# Trail-Traffic-Counter-Board.net
KiCad netlist of a schematic drawn in EAGLE
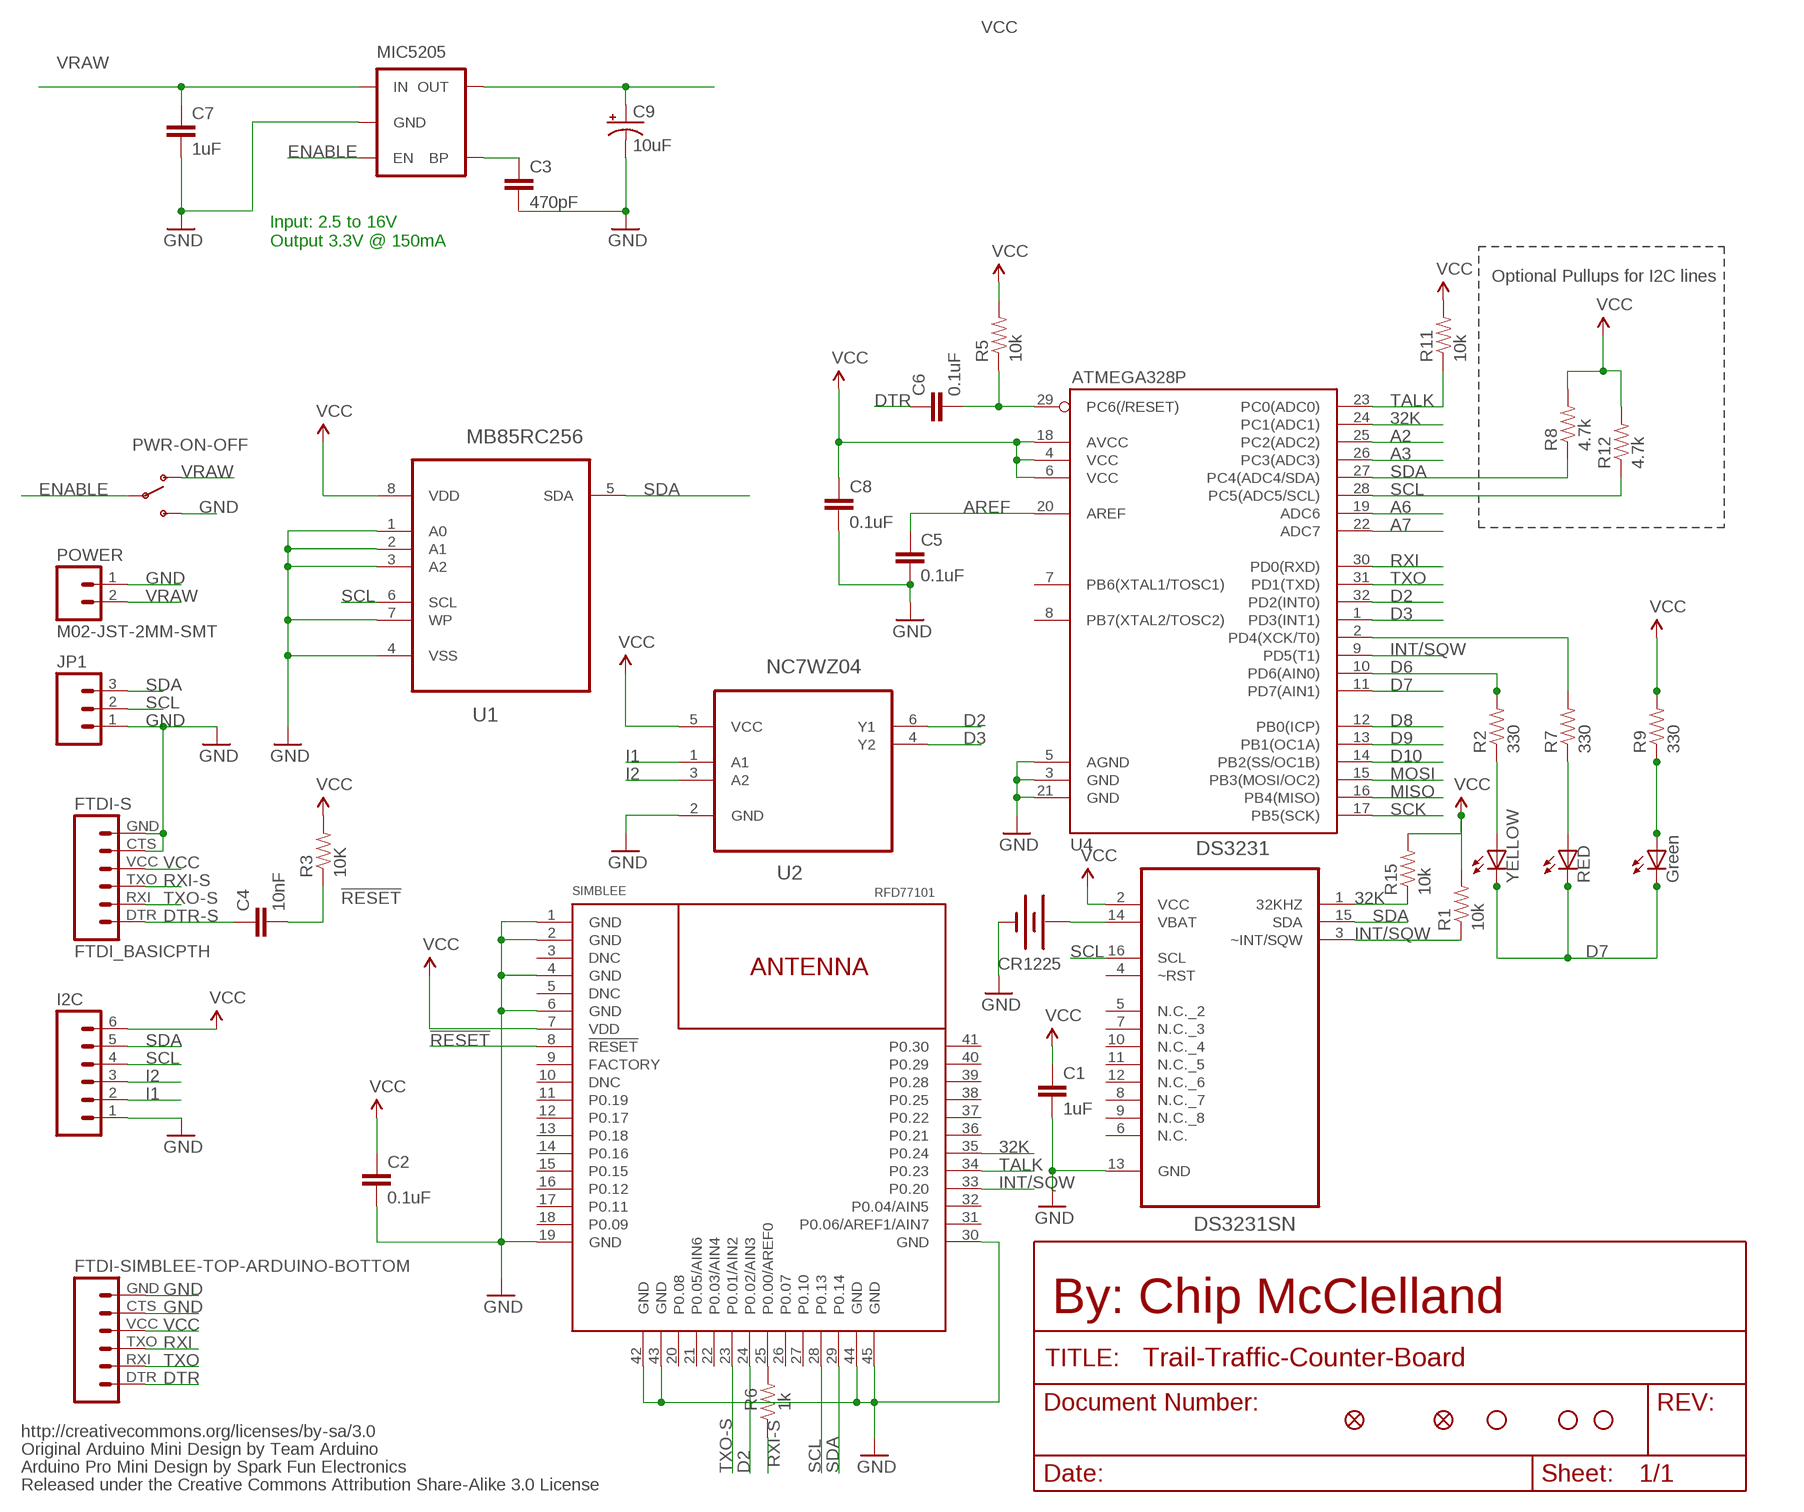
[diagram p0: schematic, sheet 1]

(export (version "E")
  (design (tool "Eeschema 10.0.6"))
  (components
    (comp (ref "ATMEGA328P")
      (value "U4")
      (footprint "eagle-import:TQFP32-08")
      (libsource (lib "eagle-import") (part "ATMEGA168"))
    )
    (comp (ref "C1")
      (value "1uF")
      (footprint "eagle-import:0805")
      (libsource (lib "eagle-import") (part "CAP0805"))
    )
    (comp (ref "C2")
      (value "0.1uF")
      (footprint "eagle-import:0805")
      (libsource (lib "eagle-import") (part "CAP0805"))
    )
    (comp (ref "C3")
      (value "470pF")
      (footprint "eagle-import:0805")
      (libsource (lib "eagle-import") (part "SparkFun-Passives_CAP0805"))
    )
    (comp (ref "C4")
      (value "10nF")
      (footprint "eagle-import:0805")
      (libsource (lib "eagle-import") (part "SparkFun-Passives_CAP0805"))
    )
    (comp (ref "C5")
      (value "0.1uF")
      (footprint "eagle-import:0805")
      (libsource (lib "eagle-import") (part "CAP0805"))
    )
    (comp (ref "C6")
      (value "0.1uF")
      (footprint "eagle-import:0805")
      (libsource (lib "eagle-import") (part "CAP0805"))
    )
    (comp (ref "C7")
      (value "1uF")
      (footprint "eagle-import:0805")
      (libsource (lib "eagle-import") (part "SparkFun-Passives_CAP0805"))
    )
    (comp (ref "C8")
      (value "0.1uF")
      (footprint "eagle-import:0805")
      (libsource (lib "eagle-import") (part "CAP0805"))
    )
    (comp (ref "C9")
      (value "10uF")
      (footprint "eagle-import:EIA3216")
      (libsource (lib "eagle-import") (part "CAP_POL1206"))
    )
    (comp (ref "CR1225")
      (value "BATTERY12MM")
      (footprint "eagle-import:BATTCON_12MM")
      (libsource (lib "eagle-import") (part "BATTERY12MM"))
    )
    (comp (ref "DS3231")
      (value "DS3231SN")
      (footprint "eagle-import:SOIC127P1032X265-16N")
      (fields (field (name "MPN") "DS3231SN#"))
      (libsource (lib "eagle-import") (part "DS3231SN"))
    )
    (comp (ref "FID1")
      (value "FIDUCIALUFIDUCIAL")
      (footprint "eagle-import:MICRO-FIDUCIAL")
      (libsource (lib "eagle-import") (part "FIDUCIALUFIDUCIAL"))
    )
    (comp (ref "FID2")
      (value "FIDUCIALUFIDUCIAL")
      (footprint "eagle-import:MICRO-FIDUCIAL")
      (libsource (lib "eagle-import") (part "FIDUCIALUFIDUCIAL"))
    )
    (comp (ref "FTDI-S")
      (value "FTDI_BASICPTH")
      (footprint "eagle-import:FTDI_BASIC")
      (libsource (lib "eagle-import") (part "FTDI_BASICPTH"))
    )
    (comp (ref "FTDI-SIMBLEE-TOP-ARDUINO-BOTTOM")
      (value "FTDI Basic")
      (footprint "eagle-import:FTDI_BASIC")
      (libsource (lib "eagle-import") (part "FTDI_BASICPTH"))
    )
    (comp (ref "G")
      (value "Green")
      (footprint "eagle-import:CHIPLED_0805")
      (libsource (lib "eagle-import") (part "LEDCHIPLED_0805"))
    )
    (comp (ref "I2C")
      (value "M06LOCK")
      (footprint "eagle-import:1X06_LOCK")
      (libsource (lib "eagle-import") (part "M06LOCK"))
    )
    (comp (ref "JP1")
      (value "M03LOCK")
      (footprint "eagle-import:1X03_LOCK")
      (libsource (lib "eagle-import") (part "M03LOCK"))
    )
    (comp (ref "JP3")
      (value "STAND-OFF")
      (footprint "eagle-import:STAND-OFF")
      (libsource (lib "eagle-import") (part "STAND-OFF"))
    )
    (comp (ref "JP4")
      (value "STAND-OFF")
      (footprint "eagle-import:STAND-OFF")
      (libsource (lib "eagle-import") (part "STAND-OFF"))
    )
    (comp (ref "JP6")
      (value "STAND-OFF")
      (footprint "eagle-import:STAND-OFF")
      (libsource (lib "eagle-import") (part "STAND-OFF"))
    )
    (comp (ref "MB85RC256")
      (value "U1")
      (footprint "eagle-import:SOIC127P600X175-8N")
      (fields (field (name "MPN") "MB85RC128PNF-G-JNE1"))
      (libsource (lib "eagle-import") (part "MB85RC128PNF-G-JNE1"))
    )
    (comp (ref "MIC5205")
      (value "MIC52053.3V")
      (footprint "eagle-import:SOT23-5")
      (libsource (lib "eagle-import") (part "MIC52053.3V"))
    )
    (comp (ref "NC7WZ04")
      (value "U2")
      (footprint "eagle-import:SOT65P210X110-6N")
      (fields (field (name "MPN") "NC7WZ04P6X"))
      (libsource (lib "eagle-import") (part "NC7WZ04P6X"))
    )
    (comp (ref "POWER")
      (value "M02-JST-2MM-SMT")
      (footprint "eagle-import:JST-2-SMD")
      (libsource (lib "eagle-import") (part "M02-JST-2MM-SMT"))
    )
    (comp (ref "PWR-ON-OFF")
      (value "SWITCH-SPDTPTH")
      (footprint "eagle-import:SWITCH-SPDT")
      (libsource (lib "eagle-import") (part "SWITCH-SPDTPTH"))
    )
    (comp (ref "R")
      (value "RED")
      (footprint "eagle-import:CHIPLED_0805")
      (libsource (lib "eagle-import") (part "LEDCHIPLED_0805"))
    )
    (comp (ref "R1")
      (value "10k")
      (footprint "eagle-import:0805")
      (libsource (lib "eagle-import") (part "RESISTOR0805-RES"))
    )
    (comp (ref "R2")
      (value "330")
      (footprint "eagle-import:0603-RES")
      (libsource (lib "eagle-import") (part "RESISTOR0603"))
    )
    (comp (ref "R3")
      (value "10K")
      (footprint "eagle-import:0805")
      (libsource (lib "eagle-import") (part "RESISTOR0805-RES"))
    )
    (comp (ref "R5")
      (value "10k")
      (footprint "eagle-import:0805")
      (libsource (lib "eagle-import") (part "RESISTOR0805-RES"))
    )
    (comp (ref "R6")
      (value "1k")
      (footprint "eagle-import:0805")
      (libsource (lib "eagle-import") (part "RESISTOR0805-RES"))
    )
    (comp (ref "R7")
      (value "330")
      (footprint "eagle-import:0603-RES")
      (libsource (lib "eagle-import") (part "RESISTOR0603"))
    )
    (comp (ref "R8")
      (value "4.7k")
      (footprint "eagle-import:0805")
      (libsource (lib "eagle-import") (part "SparkFun-Resistors_RESISTOR0805-RES"))
    )
    (comp (ref "R9")
      (value "330")
      (footprint "eagle-import:0603-RES")
      (libsource (lib "eagle-import") (part "RESISTOR0603"))
    )
    (comp (ref "R11")
      (value "10k")
      (footprint "eagle-import:0805")
      (libsource (lib "eagle-import") (part "RESISTOR0805-RES"))
    )
    (comp (ref "R12")
      (value "4.7k")
      (footprint "eagle-import:0805")
      (libsource (lib "eagle-import") (part "SparkFun-Resistors_RESISTOR0805-RES"))
    )
    (comp (ref "R15")
      (value "10k")
      (footprint "eagle-import:0805")
      (libsource (lib "eagle-import") (part "RESISTOR0805-RES"))
    )
    (comp (ref "SIMBLEE")
      (value "RFD77101")
      (footprint "eagle-import:RFD77101")
      (libsource (lib "eagle-import") (part "RFD77101"))
    )
    (comp (ref "Y")
      (value "YELLOW")
      (footprint "eagle-import:CHIPLED_0805")
      (libsource (lib "eagle-import") (part "LEDCHIPLED_0805"))
    )
  )
  (nets
    (net (code "1") (name "/32K") (class "Default")
      (node (ref "ATMEGA328P") (pin "24") (pinfunction "PC1(ADC1)_24") (pintype "bidirectional"))
      (node (ref "DS3231") (pin "1") (pinfunction "32KHZ_1") (pintype "output"))
      (node (ref "R15") (pin "1") (pinfunction "1_1") (pintype "passive"))
      (node (ref "SIMBLEE") (pin "35") (pinfunction "P0.24_35") (pintype "bidirectional"))
    )
    (net (code "2") (name "/A2") (class "Default")
      (node (ref "ATMEGA328P") (pin "25") (pinfunction "PC2(ADC2)_25") (pintype "bidirectional"))
    )
    (net (code "3") (name "/A3") (class "Default")
      (node (ref "ATMEGA328P") (pin "26") (pinfunction "PC3(ADC3)_26") (pintype "bidirectional"))
    )
    (net (code "4") (name "/A6") (class "Default")
      (node (ref "ATMEGA328P") (pin "19") (pinfunction "ADC6_19") (pintype "bidirectional"))
    )
    (net (code "5") (name "/A7") (class "Default")
      (node (ref "ATMEGA328P") (pin "22") (pinfunction "ADC7_22") (pintype "bidirectional"))
    )
    (net (code "6") (name "/AREF") (class "Default")
      (node (ref "ATMEGA328P") (pin "20") (pinfunction "AREF_20") (pintype "bidirectional"))
      (node (ref "C5") (pin "1") (pinfunction "1_1") (pintype "passive"))
    )
    (net (code "7") (name "/D2") (class "Default")
      (node (ref "ATMEGA328P") (pin "32") (pinfunction "PD2(INT0)_32") (pintype "bidirectional"))
      (node (ref "NC7WZ04") (pin "6") (pinfunction "Y1_6") (pintype "output"))
      (node (ref "SIMBLEE") (pin "24") (pinfunction "P0.02/AIN3_24") (pintype "bidirectional"))
    )
    (net (code "8") (name "/D3") (class "Default")
      (node (ref "ATMEGA328P") (pin "1") (pinfunction "PD3(INT1)_1") (pintype "bidirectional"))
      (node (ref "NC7WZ04") (pin "4") (pinfunction "Y2_4") (pintype "output"))
    )
    (net (code "9") (name "/D6") (class "Default")
      (node (ref "ATMEGA328P") (pin "10") (pinfunction "PD6(AIN0)_10") (pintype "bidirectional"))
      (node (ref "R2") (pin "2") (pinfunction "2_2") (pintype "passive"))
    )
    (net (code "10") (name "/D7") (class "Default")
      (node (ref "ATMEGA328P") (pin "11") (pinfunction "PD7(AIN1)_11") (pintype "bidirectional"))
      (node (ref "G") (pin "C") (pinfunction "C_C") (pintype "passive"))
      (node (ref "R") (pin "C") (pinfunction "C_C") (pintype "passive"))
      (node (ref "Y") (pin "C") (pinfunction "C_C") (pintype "passive"))
    )
    (net (code "11") (name "/D8") (class "Default")
      (node (ref "ATMEGA328P") (pin "12") (pinfunction "PB0(ICP)_12") (pintype "bidirectional"))
    )
    (net (code "12") (name "/D9") (class "Default")
      (node (ref "ATMEGA328P") (pin "13") (pinfunction "PB1(OC1A)_13") (pintype "bidirectional"))
    )
    (net (code "13") (name "/D10") (class "Default")
      (node (ref "ATMEGA328P") (pin "14") (pinfunction "PB2(SS/OC1B)_14") (pintype "bidirectional"))
    )
    (net (code "14") (name "/DTR") (class "Default")
      (node (ref "C6") (pin "1") (pinfunction "1_1") (pintype "passive"))
      (node (ref "FTDI-SIMBLEE-TOP-ARDUINO-BOTTOM") (pin "DTR") (pinfunction "1_DTR") (pintype "passive"))
    )
    (net (code "15") (name "/DTR-S") (class "Default")
      (node (ref "C4") (pin "1") (pinfunction "1_1") (pintype "passive"))
      (node (ref "FTDI-S") (pin "DTR") (pinfunction "1_DTR") (pintype "passive"))
    )
    (net (code "16") (name "/ENABLE") (class "Default")
      (node (ref "MIC5205") (pin "3") (pinfunction "EN_3") (pintype "input"))
      (node (ref "PWR-ON-OFF") (pin "2") (pinfunction "P_2") (pintype "passive"))
    )
    (net (code "17") (name "/I1") (class "Default")
      (node (ref "I2C") (pin "2") (pinfunction "2_2") (pintype "passive"))
      (node (ref "NC7WZ04") (pin "1") (pinfunction "A1_1") (pintype "input"))
    )
    (net (code "18") (name "/I2") (class "Default")
      (node (ref "I2C") (pin "3") (pinfunction "3_3") (pintype "passive"))
      (node (ref "NC7WZ04") (pin "3") (pinfunction "A2_3") (pintype "input"))
    )
    (net (code "19") (name "/INT{slash}SQW") (class "Default")
      (node (ref "ATMEGA328P") (pin "9") (pinfunction "PD5(T1)_9") (pintype "bidirectional"))
      (node (ref "DS3231") (pin "3") (pinfunction "~{INT/SQW}_3") (pintype "output"))
      (node (ref "R1") (pin "1") (pinfunction "1_1") (pintype "passive"))
      (node (ref "SIMBLEE") (pin "33") (pinfunction "P0.20_33") (pintype "bidirectional"))
    )
    (net (code "20") (name "/MISO") (class "Default")
      (node (ref "ATMEGA328P") (pin "16") (pinfunction "PB4(MISO)_16") (pintype "bidirectional"))
    )
    (net (code "21") (name "/MOSI") (class "Default")
      (node (ref "ATMEGA328P") (pin "15") (pinfunction "PB3(MOSI/OC2)_15") (pintype "bidirectional"))
    )
    (net (code "22") (name "/RXI") (class "Default")
      (node (ref "ATMEGA328P") (pin "30") (pinfunction "PD0(RXD)_30") (pintype "bidirectional"))
      (node (ref "FTDI-SIMBLEE-TOP-ARDUINO-BOTTOM") (pin "TXO") (pinfunction "3_TXO") (pintype "passive"))
    )
    (net (code "23") (name "/RXI-S") (class "Default")
      (node (ref "FTDI-S") (pin "TXO") (pinfunction "3_TXO") (pintype "passive"))
      (node (ref "R6") (pin "1") (pinfunction "1_1") (pintype "passive"))
    )
    (net (code "24") (name "/SCK") (class "Default")
      (node (ref "ATMEGA328P") (pin "17") (pinfunction "PB5(SCK)_17") (pintype "bidirectional"))
    )
    (net (code "25") (name "/SCL") (class "Default")
      (node (ref "ATMEGA328P") (pin "28") (pinfunction "PC5(ADC5/SCL)_28") (pintype "bidirectional"))
      (node (ref "DS3231") (pin "16") (pinfunction "SCL_16") (pintype "input"))
      (node (ref "I2C") (pin "4") (pinfunction "4_4") (pintype "passive"))
      (node (ref "JP1") (pin "2") (pinfunction "2_2") (pintype "passive"))
      (node (ref "MB85RC256") (pin "6") (pinfunction "SCL_6") (pintype "input"))
      (node (ref "R12") (pin "1") (pinfunction "1_1") (pintype "passive"))
      (node (ref "SIMBLEE") (pin "28") (pinfunction "P0.13_28") (pintype "bidirectional"))
    )
    (net (code "26") (name "/SDA") (class "Default")
      (node (ref "ATMEGA328P") (pin "27") (pinfunction "PC4(ADC4/SDA)_27") (pintype "bidirectional"))
      (node (ref "DS3231") (pin "15") (pinfunction "SDA_15") (pintype "bidirectional"))
      (node (ref "I2C") (pin "5") (pinfunction "5_5") (pintype "passive"))
      (node (ref "JP1") (pin "3") (pinfunction "3_3") (pintype "passive"))
      (node (ref "MB85RC256") (pin "5") (pinfunction "SDA_5") (pintype "bidirectional"))
      (node (ref "R8") (pin "1") (pinfunction "1_1") (pintype "passive"))
      (node (ref "SIMBLEE") (pin "29") (pinfunction "P0.14_29") (pintype "bidirectional"))
    )
    (net (code "27") (name "/TALK") (class "Default")
      (node (ref "ATMEGA328P") (pin "23") (pinfunction "PC0(ADC0)_23") (pintype "bidirectional"))
      (node (ref "R11") (pin "1") (pinfunction "1_1") (pintype "passive"))
      (node (ref "SIMBLEE") (pin "34") (pinfunction "P0.23_34") (pintype "bidirectional"))
    )
    (net (code "28") (name "/TXO") (class "Default")
      (node (ref "ATMEGA328P") (pin "31") (pinfunction "PD1(TXD)_31") (pintype "bidirectional"))
      (node (ref "FTDI-SIMBLEE-TOP-ARDUINO-BOTTOM") (pin "RXI") (pinfunction "2_RXI") (pintype "passive"))
    )
    (net (code "29") (name "/TXO-S") (class "Default")
      (node (ref "FTDI-S") (pin "RXI") (pinfunction "2_RXI") (pintype "passive"))
      (node (ref "SIMBLEE") (pin "23") (pinfunction "P0.01/AIN2_23") (pintype "bidirectional"))
    )
    (net (code "30") (name "/VRAW") (class "Default")
      (node (ref "C7") (pin "1") (pinfunction "1_1") (pintype "passive"))
      (node (ref "MIC5205") (pin "1") (pinfunction "IN_1") (pintype "input"))
      (node (ref "POWER") (pin "2") (pinfunction "1_2") (pintype "passive"))
      (node (ref "PWR-ON-OFF") (pin "1") (pinfunction "O_1") (pintype "passive"))
    )
    (net (code "31") (name "/~{RESET}") (class "Default")
      (node (ref "C4") (pin "2") (pinfunction "2_2") (pintype "passive"))
      (node (ref "R3") (pin "1") (pinfunction "1_1") (pintype "passive"))
      (node (ref "SIMBLEE") (pin "8") (pinfunction "~{RESET}_8") (pintype "input"))
    )
    (net (code "32") (name "GND") (class "Default")
      (node (ref "ATMEGA328P") (pin "21") (pinfunction "GND_21") (pintype "bidirectional"))
      (node (ref "ATMEGA328P") (pin "3") (pinfunction "GND_3") (pintype "bidirectional"))
      (node (ref "ATMEGA328P") (pin "5") (pinfunction "AGND_5") (pintype "bidirectional"))
      (node (ref "C1") (pin "2") (pinfunction "2_2") (pintype "passive"))
      (node (ref "C2") (pin "2") (pinfunction "2_2") (pintype "passive"))
      (node (ref "C3") (pin "2") (pinfunction "2_2") (pintype "passive"))
      (node (ref "C5") (pin "2") (pinfunction "2_2") (pintype "passive"))
      (node (ref "C7") (pin "2") (pinfunction "2_2") (pintype "passive"))
      (node (ref "C8") (pin "2") (pinfunction "2_2") (pintype "passive"))
      (node (ref "C9") (pin "C") (pinfunction "-_C") (pintype "passive"))
      (node (ref "CR1225") (pin "GND") (pinfunction "-_GND") (pintype "power_in"))
      (node (ref "DS3231") (pin "13") (pinfunction "GND_13") (pintype "passive"))
      (node (ref "FTDI-S") (pin "CTS") (pinfunction "5_CTS") (pintype "passive"))
      (node (ref "FTDI-S") (pin "GND") (pinfunction "6_GND") (pintype "passive"))
      (node (ref "FTDI-SIMBLEE-TOP-ARDUINO-BOTTOM") (pin "CTS") (pinfunction "5_CTS") (pintype "passive"))
      (node (ref "FTDI-SIMBLEE-TOP-ARDUINO-BOTTOM") (pin "GND") (pinfunction "6_GND") (pintype "passive"))
      (node (ref "I2C") (pin "1") (pinfunction "1_1") (pintype "passive"))
      (node (ref "JP1") (pin "1") (pinfunction "1_1") (pintype "passive"))
      (node (ref "MB85RC256") (pin "1") (pinfunction "A0_1") (pintype "input"))
      (node (ref "MB85RC256") (pin "2") (pinfunction "A1_2") (pintype "input"))
      (node (ref "MB85RC256") (pin "3") (pinfunction "A2_3") (pintype "input"))
      (node (ref "MB85RC256") (pin "4") (pinfunction "VSS_4") (pintype "passive"))
      (node (ref "MB85RC256") (pin "7") (pinfunction "WP_7") (pintype "input"))
      (node (ref "MIC5205") (pin "2") (pinfunction "GND_2") (pintype "input"))
      (node (ref "NC7WZ04") (pin "2") (pinfunction "GND_2") (pintype "passive"))
      (node (ref "POWER") (pin "1") (pinfunction "2_1") (pintype "passive"))
      (node (ref "PWR-ON-OFF") (pin "3") (pinfunction "S_3") (pintype "passive"))
      (node (ref "SIMBLEE") (pin "1") (pinfunction "GND_1") (pintype "power_in"))
      (node (ref "SIMBLEE") (pin "19") (pinfunction "GND_19") (pintype "power_in"))
      (node (ref "SIMBLEE") (pin "2") (pinfunction "GND_2") (pintype "power_in"))
      (node (ref "SIMBLEE") (pin "30") (pinfunction "GND_30") (pintype "power_in"))
      (node (ref "SIMBLEE") (pin "4") (pinfunction "GND_4") (pintype "power_in"))
      (node (ref "SIMBLEE") (pin "42") (pinfunction "GND_42") (pintype "power_in"))
      (node (ref "SIMBLEE") (pin "43") (pinfunction "GND_43") (pintype "power_in"))
      (node (ref "SIMBLEE") (pin "44") (pinfunction "GND_44") (pintype "power_in"))
      (node (ref "SIMBLEE") (pin "45") (pinfunction "GND_45") (pintype "power_in"))
      (node (ref "SIMBLEE") (pin "6") (pinfunction "GND_6") (pintype "power_in"))
    )
    (net (code "33") (name "Net-(ATMEGA328P-PC6({slash}RESET))") (class "Default")
      (node (ref "ATMEGA328P") (pin "29") (pinfunction "PC6(/RESET)_29") (pintype "bidirectional"))
      (node (ref "C6") (pin "2") (pinfunction "2_2") (pintype "passive"))
      (node (ref "R5") (pin "1") (pinfunction "1_1") (pintype "passive"))
    )
    (net (code "34") (name "Net-(ATMEGA328P-PD4(XCK{slash}T0))") (class "Default")
      (node (ref "ATMEGA328P") (pin "2") (pinfunction "PD4(XCK/T0)_2") (pintype "bidirectional"))
      (node (ref "R7") (pin "2") (pinfunction "2_2") (pintype "passive"))
    )
    (net (code "35") (name "Net-(CR1225-+)") (class "Default")
      (node (ref "CR1225") (pin "PWR@1") (pinfunction "+_PWR@1") (pintype "power_in"))
      (node (ref "DS3231") (pin "14") (pinfunction "VBAT_14") (pintype "power_in"))
    )
    (net (code "36") (name "Net-(G-PadA)") (class "Default")
      (node (ref "G") (pin "A") (pinfunction "A_A") (pintype "passive"))
      (node (ref "R9") (pin "1") (pinfunction "1_1") (pintype "passive"))
    )
    (net (code "37") (name "Net-(MIC5205-BP)") (class "Default")
      (node (ref "C3") (pin "1") (pinfunction "1_1") (pintype "passive"))
      (node (ref "MIC5205") (pin "4") (pinfunction "BP_4") (pintype "input"))
    )
    (net (code "38") (name "Net-(R-PadA)") (class "Default")
      (node (ref "R") (pin "A") (pinfunction "A_A") (pintype "passive"))
      (node (ref "R7") (pin "1") (pinfunction "1_1") (pintype "passive"))
    )
    (net (code "39") (name "Net-(R2-Pad1)") (class "Default")
      (node (ref "R2") (pin "1") (pinfunction "1_1") (pintype "passive"))
      (node (ref "Y") (pin "A") (pinfunction "A_A") (pintype "passive"))
    )
    (net (code "40") (name "Net-(SIMBLEE-P0.00{slash}AREF0)") (class "Default")
      (node (ref "R6") (pin "2") (pinfunction "2_2") (pintype "passive"))
      (node (ref "SIMBLEE") (pin "25") (pinfunction "P0.00/AREF0_25") (pintype "bidirectional"))
    )
    (net (code "41") (name "VCC") (class "Default")
      (node (ref "ATMEGA328P") (pin "18") (pinfunction "AVCC_18") (pintype "bidirectional"))
      (node (ref "ATMEGA328P") (pin "4") (pinfunction "VCC_4") (pintype "bidirectional"))
      (node (ref "ATMEGA328P") (pin "6") (pinfunction "VCC_6") (pintype "bidirectional"))
      (node (ref "C1") (pin "1") (pinfunction "1_1") (pintype "passive"))
      (node (ref "C2") (pin "1") (pinfunction "1_1") (pintype "passive"))
      (node (ref "C8") (pin "1") (pinfunction "1_1") (pintype "passive"))
      (node (ref "C9") (pin "A") (pinfunction "+_A") (pintype "passive"))
      (node (ref "DS3231") (pin "2") (pinfunction "VCC_2") (pintype "power_in"))
      (node (ref "FTDI-S") (pin "VCC") (pinfunction "4_VCC") (pintype "passive"))
      (node (ref "FTDI-SIMBLEE-TOP-ARDUINO-BOTTOM") (pin "VCC") (pinfunction "4_VCC") (pintype "passive"))
      (node (ref "I2C") (pin "6") (pinfunction "6_6") (pintype "passive"))
      (node (ref "MB85RC256") (pin "8") (pinfunction "VDD_8") (pintype "power_in"))
      (node (ref "MIC5205") (pin "5") (pinfunction "OUT_5") (pintype "passive"))
      (node (ref "NC7WZ04") (pin "5") (pinfunction "VCC_5") (pintype "power_in"))
      (node (ref "R1") (pin "2") (pinfunction "2_2") (pintype "passive"))
      (node (ref "R11") (pin "2") (pinfunction "2_2") (pintype "passive"))
      (node (ref "R12") (pin "2") (pinfunction "2_2") (pintype "passive"))
      (node (ref "R15") (pin "2") (pinfunction "2_2") (pintype "passive"))
      (node (ref "R3") (pin "2") (pinfunction "2_2") (pintype "passive"))
      (node (ref "R5") (pin "2") (pinfunction "2_2") (pintype "passive"))
      (node (ref "R8") (pin "2") (pinfunction "2_2") (pintype "passive"))
      (node (ref "R9") (pin "2") (pinfunction "2_2") (pintype "passive"))
      (node (ref "SIMBLEE") (pin "7") (pinfunction "VDD_7") (pintype "power_in"))
    )
    (net (code "42") (name "unconnected-(ATMEGA328P-PB6(XTAL1{slash}TOSC1)-Pad7)") (class "Default")
      (node (ref "ATMEGA328P") (pin "7") (pinfunction "PB6(XTAL1/TOSC1)_7") (pintype "bidirectional"))
    )
    (net (code "43") (name "unconnected-(ATMEGA328P-PB7(XTAL2{slash}TOSC2)-Pad8)") (class "Default")
      (node (ref "ATMEGA328P") (pin "8") (pinfunction "PB7(XTAL2/TOSC2)_8") (pintype "bidirectional"))
    )
    (net (code "44") (name "unconnected-(DS3231-N.C.-Pad6)") (class "Default")
      (node (ref "DS3231") (pin "6") (pinfunction "N.C._6") (pintype "no_connect"))
    )
    (net (code "45") (name "unconnected-(DS3231-N.C._2-Pad5)") (class "Default")
      (node (ref "DS3231") (pin "5") (pinfunction "N.C._2_5") (pintype "no_connect"))
    )
    (net (code "46") (name "unconnected-(DS3231-N.C._3-Pad7)") (class "Default")
      (node (ref "DS3231") (pin "7") (pinfunction "N.C._3_7") (pintype "no_connect"))
    )
    (net (code "47") (name "unconnected-(DS3231-N.C._4-Pad10)") (class "Default")
      (node (ref "DS3231") (pin "10") (pinfunction "N.C._4_10") (pintype "no_connect"))
    )
    (net (code "48") (name "unconnected-(DS3231-N.C._5-Pad11)") (class "Default")
      (node (ref "DS3231") (pin "11") (pinfunction "N.C._5_11") (pintype "no_connect"))
    )
    (net (code "49") (name "unconnected-(DS3231-N.C._6-Pad12)") (class "Default")
      (node (ref "DS3231") (pin "12") (pinfunction "N.C._6_12") (pintype "no_connect"))
    )
    (net (code "50") (name "unconnected-(DS3231-N.C._7-Pad8)") (class "Default")
      (node (ref "DS3231") (pin "8") (pinfunction "N.C._7_8") (pintype "no_connect"))
    )
    (net (code "51") (name "unconnected-(DS3231-N.C._8-Pad9)") (class "Default")
      (node (ref "DS3231") (pin "9") (pinfunction "N.C._8_9") (pintype "no_connect"))
    )
    (net (code "52") (name "unconnected-(DS3231-~{RST}-Pad4)") (class "Default")
      (node (ref "DS3231") (pin "4") (pinfunction "~{RST}_4") (pintype "bidirectional"))
    )
    (net (code "53") (name "unconnected-(SIMBLEE-DNC-Pad3)") (class "Default")
      (node (ref "SIMBLEE") (pin "3") (pinfunction "DNC_3") (pintype "no_connect"))
    )
    (net (code "54") (name "unconnected-(SIMBLEE-DNC-Pad5)") (class "Default")
      (node (ref "SIMBLEE") (pin "5") (pinfunction "DNC_5") (pintype "no_connect"))
    )
    (net (code "55") (name "unconnected-(SIMBLEE-DNC-Pad10)") (class "Default")
      (node (ref "SIMBLEE") (pin "10") (pinfunction "DNC_10") (pintype "no_connect"))
    )
    (net (code "56") (name "unconnected-(SIMBLEE-FACTORY-Pad9)") (class "Default")
      (node (ref "SIMBLEE") (pin "9") (pinfunction "FACTORY_9") (pintype "no_connect"))
    )
    (net (code "57") (name "unconnected-(SIMBLEE-P0.03{slash}AIN4-Pad22)") (class "Default")
      (node (ref "SIMBLEE") (pin "22") (pinfunction "P0.03/AIN4_22") (pintype "bidirectional"))
    )
    (net (code "58") (name "unconnected-(SIMBLEE-P0.04{slash}AIN5-Pad32)") (class "Default")
      (node (ref "SIMBLEE") (pin "32") (pinfunction "P0.04/AIN5_32") (pintype "bidirectional"))
    )
    (net (code "59") (name "unconnected-(SIMBLEE-P0.05{slash}AIN6-Pad21)") (class "Default")
      (node (ref "SIMBLEE") (pin "21") (pinfunction "P0.05/AIN6_21") (pintype "bidirectional"))
    )
    (net (code "60") (name "unconnected-(SIMBLEE-P0.06{slash}AREF1{slash}AIN7-Pad31)") (class "Default")
      (node (ref "SIMBLEE") (pin "31") (pinfunction "P0.06/AREF1/AIN7_31") (pintype "bidirectional"))
    )
    (net (code "61") (name "unconnected-(SIMBLEE-P0.07-Pad26)") (class "Default")
      (node (ref "SIMBLEE") (pin "26") (pinfunction "P0.07_26") (pintype "bidirectional"))
    )
    (net (code "62") (name "unconnected-(SIMBLEE-P0.08-Pad20)") (class "Default")
      (node (ref "SIMBLEE") (pin "20") (pinfunction "P0.08_20") (pintype "bidirectional"))
    )
    (net (code "63") (name "unconnected-(SIMBLEE-P0.09-Pad18)") (class "Default")
      (node (ref "SIMBLEE") (pin "18") (pinfunction "P0.09_18") (pintype "bidirectional"))
    )
    (net (code "64") (name "unconnected-(SIMBLEE-P0.10-Pad27)") (class "Default")
      (node (ref "SIMBLEE") (pin "27") (pinfunction "P0.10_27") (pintype "bidirectional"))
    )
    (net (code "65") (name "unconnected-(SIMBLEE-P0.11-Pad17)") (class "Default")
      (node (ref "SIMBLEE") (pin "17") (pinfunction "P0.11_17") (pintype "bidirectional"))
    )
    (net (code "66") (name "unconnected-(SIMBLEE-P0.12-Pad16)") (class "Default")
      (node (ref "SIMBLEE") (pin "16") (pinfunction "P0.12_16") (pintype "bidirectional"))
    )
    (net (code "67") (name "unconnected-(SIMBLEE-P0.15-Pad15)") (class "Default")
      (node (ref "SIMBLEE") (pin "15") (pinfunction "P0.15_15") (pintype "bidirectional"))
    )
    (net (code "68") (name "unconnected-(SIMBLEE-P0.16-Pad14)") (class "Default")
      (node (ref "SIMBLEE") (pin "14") (pinfunction "P0.16_14") (pintype "bidirectional"))
    )
    (net (code "69") (name "unconnected-(SIMBLEE-P0.17-Pad12)") (class "Default")
      (node (ref "SIMBLEE") (pin "12") (pinfunction "P0.17_12") (pintype "bidirectional"))
    )
    (net (code "70") (name "unconnected-(SIMBLEE-P0.18-Pad13)") (class "Default")
      (node (ref "SIMBLEE") (pin "13") (pinfunction "P0.18_13") (pintype "bidirectional"))
    )
    (net (code "71") (name "unconnected-(SIMBLEE-P0.19-Pad11)") (class "Default")
      (node (ref "SIMBLEE") (pin "11") (pinfunction "P0.19_11") (pintype "bidirectional"))
    )
    (net (code "72") (name "unconnected-(SIMBLEE-P0.21-Pad36)") (class "Default")
      (node (ref "SIMBLEE") (pin "36") (pinfunction "P0.21_36") (pintype "bidirectional"))
    )
    (net (code "73") (name "unconnected-(SIMBLEE-P0.22-Pad37)") (class "Default")
      (node (ref "SIMBLEE") (pin "37") (pinfunction "P0.22_37") (pintype "bidirectional"))
    )
    (net (code "74") (name "unconnected-(SIMBLEE-P0.25-Pad38)") (class "Default")
      (node (ref "SIMBLEE") (pin "38") (pinfunction "P0.25_38") (pintype "bidirectional"))
    )
    (net (code "75") (name "unconnected-(SIMBLEE-P0.28-Pad39)") (class "Default")
      (node (ref "SIMBLEE") (pin "39") (pinfunction "P0.28_39") (pintype "bidirectional"))
    )
    (net (code "76") (name "unconnected-(SIMBLEE-P0.29-Pad40)") (class "Default")
      (node (ref "SIMBLEE") (pin "40") (pinfunction "P0.29_40") (pintype "bidirectional"))
    )
    (net (code "77") (name "unconnected-(SIMBLEE-P0.30-Pad41)") (class "Default")
      (node (ref "SIMBLEE") (pin "41") (pinfunction "P0.30_41") (pintype "bidirectional"))
    )
  )
)
